# Vario_Kobo.net
KiCad netlist of a schematic drawn in EAGLE
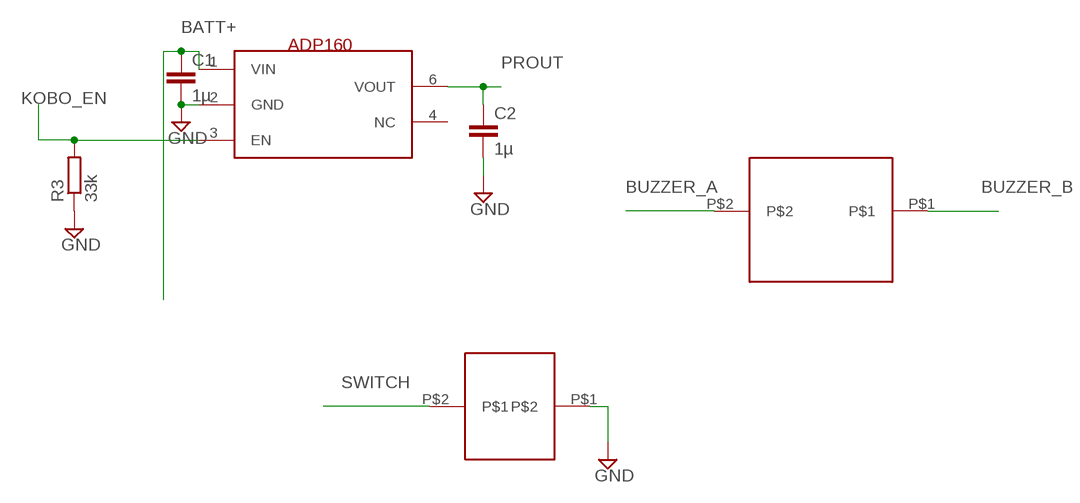
[diagram p0: schematic, sheet 1]
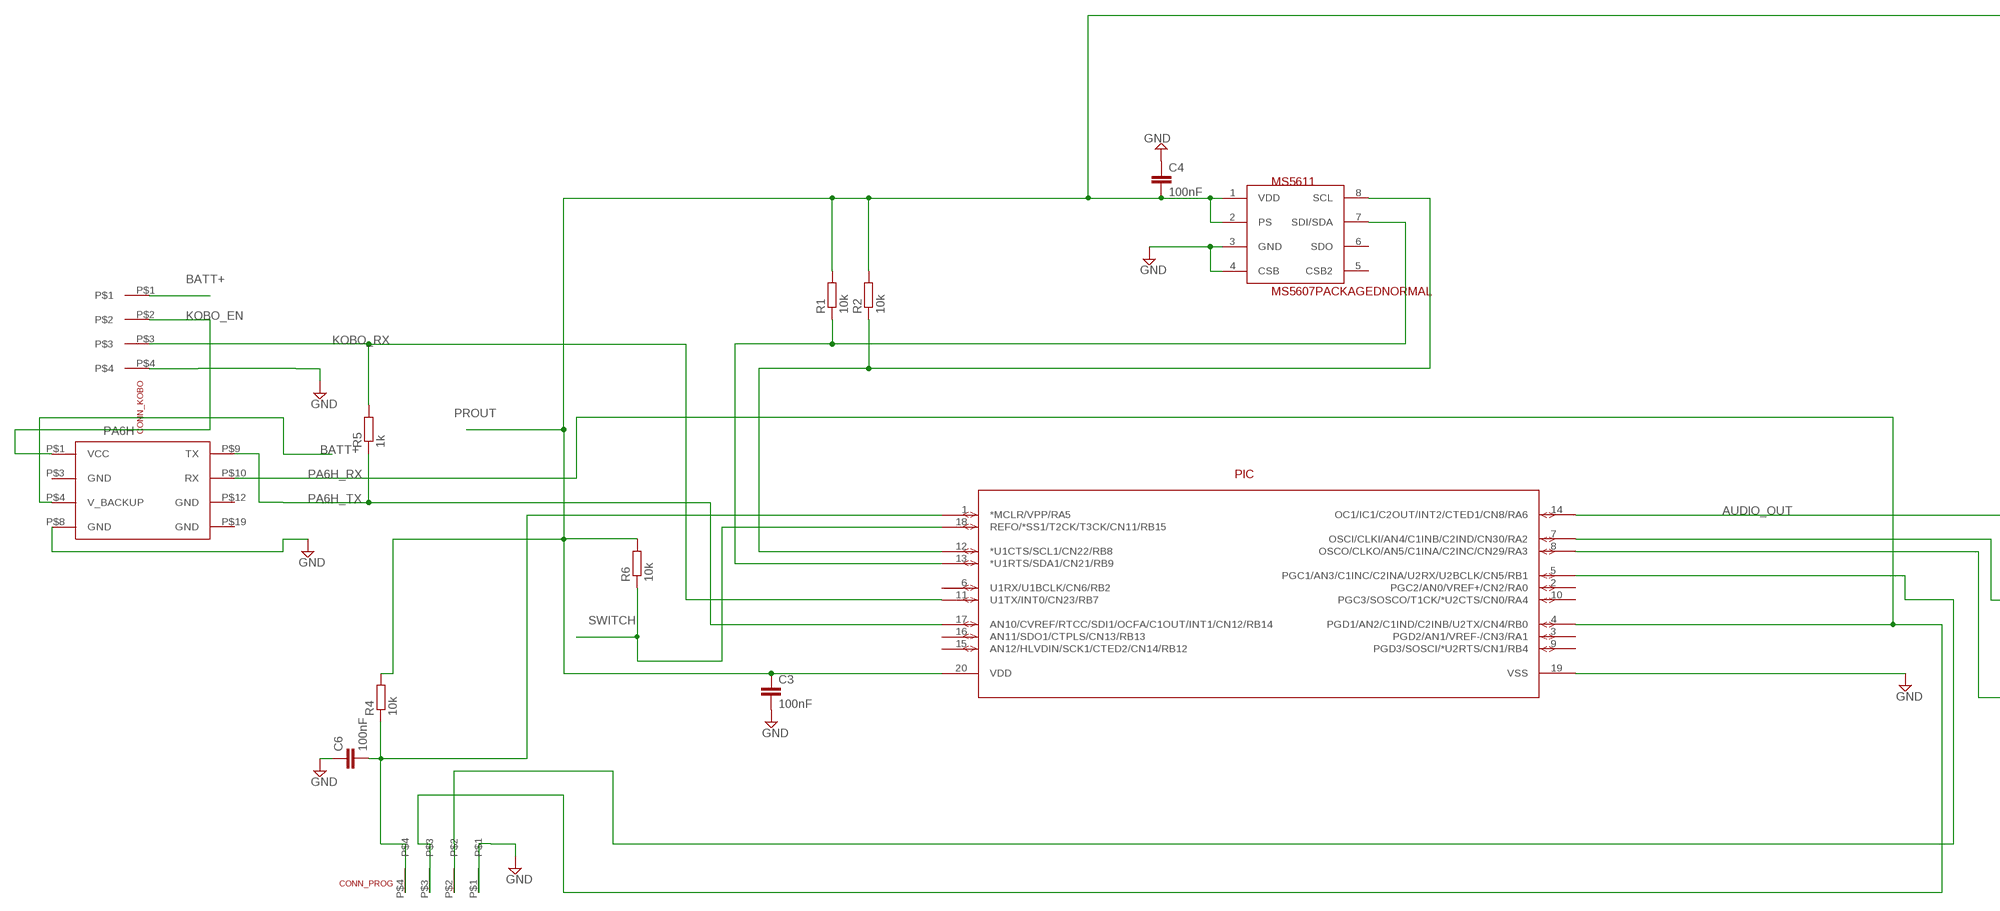
[diagram p1: schematic, sheet 2, part 1 of 2]
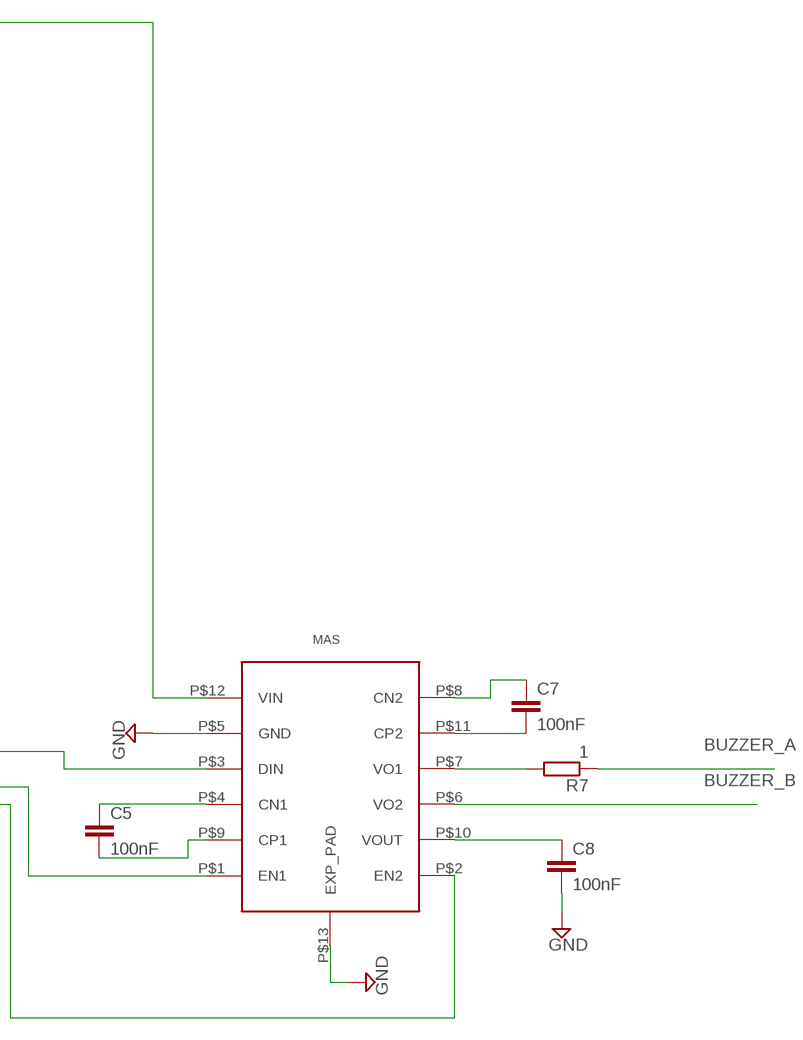
[diagram p2: schematic, sheet 2, part 2 of 2]

(export (version "E")
  (design (tool "Eeschema 10.0.6"))
  (components
    (comp (ref "ADP160")
      (value "ADP160/161/162/163")
      (footprint "eagle-import:TSOT23-6_DDC")
      (libsource (lib "eagle-import") (part "ADP160/161/162/163"))
    )
    (comp (ref "BUTTON")
      (value "SMS_J_LEAD")
      (footprint "eagle-import:SMS_J_LEAD")
      (libsource (lib "eagle-import") (part "SMS_J_LEAD"))
    )
    (comp (ref "BUZZER")
      (value "PKLCS1212E2000-R1")
      (footprint "eagle-import:PKLCS1212E2000-R1-SMD")
      (libsource (lib "eagle-import") (part "PKLCS1212E2000-R1"))
    )
    (comp (ref "C1")
      (value "1µ")
      (footprint "eagle-import:C0603")
      (libsource (lib "eagle-import") (part "C-EUC0603"))
    )
    (comp (ref "C2")
      (value "1µ")
      (footprint "eagle-import:C0603")
      (libsource (lib "eagle-import") (part "C-EUC0603"))
    )
    (comp (ref "R3")
      (value "33k")
      (footprint "eagle-import:R0603")
      (libsource (lib "eagle-import") (part "R-EU_R0603"))
    )
    (comp (ref "C3")
      (value "100nF")
      (footprint "eagle-import:C0603")
      (libsource (lib "eagle-import") (part "C-EUC0603"))
    )
    (comp (ref "C4")
      (value "100nF")
      (footprint "eagle-import:C0603")
      (libsource (lib "eagle-import") (part "C-EUC0603"))
    )
    (comp (ref "C5")
      (value "100nF")
      (footprint "eagle-import:C0603")
      (libsource (lib "eagle-import") (part "C-EUC0603"))
    )
    (comp (ref "C6")
      (value "100nF")
      (footprint "eagle-import:C0603")
      (libsource (lib "eagle-import") (part "C-EUC0603"))
    )
    (comp (ref "C7")
      (value "100nF")
      (footprint "eagle-import:C0603")
      (libsource (lib "eagle-import") (part "C-EUC0603"))
    )
    (comp (ref "C8")
      (value "100nF")
      (footprint "eagle-import:C0603")
      (libsource (lib "eagle-import") (part "C-EUC0603"))
    )
    (comp (ref "CONN_KOBO")
      (value "PICO-EZMATE4")
      (footprint "eagle-import:PICO-EZMATE4-PCB")
      (libsource (lib "eagle-import") (part "PICO-EZMATE4"))
    )
    (comp (ref "CONN_PROG")
      (value "PICO-EZMATE4")
      (footprint "eagle-import:PICO-EZMATE4-PCB")
      (libsource (lib "eagle-import") (part "PICO-EZMATE4"))
    )
    (comp (ref "MAS")
      (value "MAS6240")
      (footprint "eagle-import:QFN12_3X3_LONGPADS")
      (libsource (lib "eagle-import") (part "MAS6240"))
    )
    (comp (ref "MS5611")
      (value "MS5607PACKAGEDNORMAL")
      (footprint "eagle-import:MS5607-02BA03")
      (libsource (lib "eagle-import") (part "MS5607PACKAGEDNORMAL"))
    )
    (comp (ref "PA6H")
      (value "PA6H")
      (footprint "eagle-import:PA6H_PRINT")
      (libsource (lib "eagle-import") (part "PA6H"))
    )
    (comp (ref "PIC")
      (value "PIC24F16KA101-X_")
      (footprint "eagle-import:SSOP20_MC")
      (libsource (lib "eagle-import") (part "PIC24F16KA101-X_"))
    )
    (comp (ref "R1")
      (value "10k")
      (footprint "eagle-import:R0603")
      (libsource (lib "eagle-import") (part "R-EU_R0603"))
    )
    (comp (ref "R2")
      (value "10k")
      (footprint "eagle-import:R0603")
      (libsource (lib "eagle-import") (part "R-EU_R0603"))
    )
    (comp (ref "R4")
      (value "10k")
      (footprint "eagle-import:R0603")
      (libsource (lib "eagle-import") (part "R-EU_R0603"))
    )
    (comp (ref "R5")
      (value "1k")
      (footprint "eagle-import:R0603")
      (libsource (lib "eagle-import") (part "R-EU_R0603"))
    )
    (comp (ref "R6")
      (value "10k")
      (footprint "eagle-import:R0603")
      (libsource (lib "eagle-import") (part "R-EU_R0603"))
    )
    (comp (ref "R7")
      (value "1")
      (footprint "eagle-import:R0603")
      (libsource (lib "eagle-import") (part "R-EU_R0603"))
    )
  )
  (nets
    (net (code "1") (name "AUDIO_OUT") (class "Default")
      (node (ref "MAS") (pin "P$3") (pinfunction "DIN_P$3") (pintype "bidirectional"))
      (node (ref "PIC") (pin "14") (pinfunction "OC1/IC1/C2OUT/INT2/CTED1/CN8/RA6_14") (pintype "passive"))
    )
    (net (code "2") (name "BATT+") (class "Default")
      (node (ref "ADP160") (pin "1") (pinfunction "VIN_1") (pintype "tri_state"))
      (node (ref "C1") (pin "1") (pinfunction "1_1") (pintype "passive"))
      (node (ref "CONN_KOBO") (pin "P$1") (pinfunction "P$1_P$1") (pintype "bidirectional"))
      (node (ref "PA6H") (pin "P$4") (pinfunction "V_BACKUP_P$4") (pintype "bidirectional"))
    )
    (net (code "3") (name "BUZZER_A") (class "Default")
      (node (ref "BUZZER") (pin "P$2") (pinfunction "P$2_P$2") (pintype "bidirectional"))
      (node (ref "R7") (pin "1") (pinfunction "1_1") (pintype "passive"))
    )
    (net (code "4") (name "BUZZER_B") (class "Default")
      (node (ref "BUZZER") (pin "P$1") (pinfunction "P$1_P$1") (pintype "bidirectional"))
      (node (ref "MAS") (pin "P$6") (pinfunction "VO2_P$6") (pintype "bidirectional"))
    )
    (net (code "5") (name "GND") (class "Default")
      (node (ref "ADP160") (pin "2") (pinfunction "GND_2") (pintype "power_in"))
      (node (ref "BUTTON") (pin "P$1") (pinfunction "P$2_P$1") (pintype "bidirectional"))
      (node (ref "C1") (pin "2") (pinfunction "2_2") (pintype "passive"))
      (node (ref "C2") (pin "2") (pinfunction "2_2") (pintype "passive"))
      (node (ref "C3") (pin "2") (pinfunction "2_2") (pintype "passive"))
      (node (ref "C4") (pin "1") (pinfunction "1_1") (pintype "passive"))
      (node (ref "C6") (pin "1") (pinfunction "1_1") (pintype "passive"))
      (node (ref "C8") (pin "2") (pinfunction "2_2") (pintype "passive"))
      (node (ref "CONN_KOBO") (pin "P$4") (pinfunction "P$4_P$4") (pintype "bidirectional"))
      (node (ref "CONN_PROG") (pin "P$1") (pinfunction "P$1_P$1") (pintype "bidirectional"))
      (node (ref "MAS") (pin "P$13") (pinfunction "EXP_PAD_P$13") (pintype "bidirectional"))
      (node (ref "MAS") (pin "P$5") (pinfunction "GND_P$5") (pintype "bidirectional"))
      (node (ref "MS5611") (pin "3") (pinfunction "GND_3") (pintype "power_in"))
      (node (ref "MS5611") (pin "4") (pinfunction "CSB_4") (pintype "input"))
      (node (ref "PA6H") (pin "P$8") (pinfunction "GND_P$8") (pintype "bidirectional"))
      (node (ref "PIC") (pin "19") (pinfunction "VSS_19") (pintype "passive"))
      (node (ref "R3") (pin "1") (pinfunction "1_1") (pintype "passive"))
    )
    (net (code "6") (name "KOBO_EN") (class "Default")
      (node (ref "ADP160") (pin "3") (pinfunction "EN_3") (pintype "input"))
      (node (ref "CONN_KOBO") (pin "P$2") (pinfunction "P$2_P$2") (pintype "bidirectional"))
      (node (ref "PA6H") (pin "P$1") (pinfunction "VCC_P$1") (pintype "bidirectional"))
      (node (ref "R3") (pin "2") (pinfunction "2_2") (pintype "passive"))
    )
    (net (code "7") (name "KOBO_RX") (class "Default")
      (node (ref "CONN_KOBO") (pin "P$3") (pinfunction "P$3_P$3") (pintype "bidirectional"))
      (node (ref "PIC") (pin "11") (pinfunction "U1TX/INT0/CN23/RB7_11") (pintype "passive"))
      (node (ref "R5") (pin "2") (pinfunction "2_2") (pintype "passive"))
    )
    (net (code "8") (name "Net-(MAS-CN1)") (class "Default")
      (node (ref "C5") (pin "1") (pinfunction "1_1") (pintype "passive"))
      (node (ref "MAS") (pin "P$4") (pinfunction "CN1_P$4") (pintype "bidirectional"))
    )
    (net (code "9") (name "Net-(MAS-CN2)") (class "Default")
      (node (ref "C7") (pin "1") (pinfunction "1_1") (pintype "passive"))
      (node (ref "MAS") (pin "P$8") (pinfunction "CN2_P$8") (pintype "bidirectional"))
    )
    (net (code "10") (name "Net-(MAS-CP1)") (class "Default")
      (node (ref "C5") (pin "2") (pinfunction "2_2") (pintype "passive"))
      (node (ref "MAS") (pin "P$9") (pinfunction "CP1_P$9") (pintype "bidirectional"))
    )
    (net (code "11") (name "Net-(MAS-CP2)") (class "Default")
      (node (ref "C7") (pin "2") (pinfunction "2_2") (pintype "passive"))
      (node (ref "MAS") (pin "P$11") (pinfunction "CP2_P$11") (pintype "bidirectional"))
    )
    (net (code "12") (name "Net-(MAS-EN1)") (class "Default")
      (node (ref "MAS") (pin "P$1") (pinfunction "EN1_P$1") (pintype "bidirectional"))
      (node (ref "PIC") (pin "7") (pinfunction "OSCI/CLKI/AN4/C1INB/C2IND/CN30/RA2_7") (pintype "passive"))
    )
    (net (code "13") (name "Net-(MAS-EN2)") (class "Default")
      (node (ref "MAS") (pin "P$2") (pinfunction "EN2_P$2") (pintype "bidirectional"))
      (node (ref "PIC") (pin "8") (pinfunction "OSCO/CLKO/AN5/C1INA/C2INC/CN29/RA3_8") (pintype "passive"))
    )
    (net (code "14") (name "Net-(MAS-VO1)") (class "Default")
      (node (ref "MAS") (pin "P$7") (pinfunction "VO1_P$7") (pintype "bidirectional"))
      (node (ref "R7") (pin "2") (pinfunction "2_2") (pintype "passive"))
    )
    (net (code "15") (name "Net-(MAS-VOUT)") (class "Default")
      (node (ref "C8") (pin "1") (pinfunction "1_1") (pintype "passive"))
      (node (ref "MAS") (pin "P$10") (pinfunction "VOUT_P$10") (pintype "bidirectional"))
    )
    (net (code "16") (name "Net-(MS5611-SCL)") (class "Default")
      (node (ref "MS5611") (pin "8") (pinfunction "SCL_8") (pintype "input"))
      (node (ref "PIC") (pin "12") (pinfunction "*U1CTS/SCL1/CN22/RB8_12") (pintype "passive"))
      (node (ref "R2") (pin "1") (pinfunction "1_1") (pintype "passive"))
    )
    (net (code "17") (name "Net-(MS5611-SDI{slash}SDA)") (class "Default")
      (node (ref "MS5611") (pin "7") (pinfunction "SDI/SDA_7") (pintype "bidirectional"))
      (node (ref "PIC") (pin "13") (pinfunction "*U1RTS/SDA1/CN21/RB9_13") (pintype "passive"))
      (node (ref "R1") (pin "1") (pinfunction "1_1") (pintype "passive"))
    )
    (net (code "18") (name "Net-(PIC-*MCLR{slash}VPP{slash}RA5)") (class "Default")
      (node (ref "C6") (pin "2") (pinfunction "2_2") (pintype "passive"))
      (node (ref "CONN_PROG") (pin "P$4") (pinfunction "P$4_P$4") (pintype "bidirectional"))
      (node (ref "PIC") (pin "1") (pinfunction "*MCLR/VPP/RA5_1") (pintype "passive"))
      (node (ref "R4") (pin "1") (pinfunction "1_1") (pintype "passive"))
    )
    (net (code "19") (name "Net-(PIC-PGC1{slash}AN3{slash}C1INC{slash}C2INA{slash}U2RX{slash}U2BCLK{slash}CN5{slash}RB1)") (class "Default")
      (node (ref "CONN_PROG") (pin "P$2") (pinfunction "P$2_P$2") (pintype "bidirectional"))
      (node (ref "PIC") (pin "5") (pinfunction "PGC1/AN3/C1INC/C2INA/U2RX/U2BCLK/CN5/RB1_5") (pintype "passive"))
    )
    (net (code "20") (name "PA6H_RX") (class "Default")
      (node (ref "CONN_PROG") (pin "P$3") (pinfunction "P$3_P$3") (pintype "bidirectional"))
      (node (ref "PA6H") (pin "P$10") (pinfunction "RX_P$10") (pintype "bidirectional"))
      (node (ref "PIC") (pin "4") (pinfunction "PGD1/AN2/C1IND/C2INB/U2TX/CN4/RB0_4") (pintype "passive"))
    )
    (net (code "21") (name "PA6H_TX") (class "Default")
      (node (ref "PA6H") (pin "P$9") (pinfunction "TX_P$9") (pintype "bidirectional"))
      (node (ref "PIC") (pin "17") (pinfunction "AN10/CVREF/RTCC/SDI1/OCFA/C1OUT/INT1/CN12/RB14_17") (pintype "passive"))
      (node (ref "R5") (pin "1") (pinfunction "1_1") (pintype "passive"))
    )
    (net (code "22") (name "PROUT") (class "Default")
      (node (ref "ADP160") (pin "6") (pinfunction "VOUT_6") (pintype "bidirectional"))
      (node (ref "C2") (pin "1") (pinfunction "1_1") (pintype "passive"))
      (node (ref "C3") (pin "1") (pinfunction "1_1") (pintype "passive"))
      (node (ref "C4") (pin "2") (pinfunction "2_2") (pintype "passive"))
      (node (ref "MAS") (pin "P$12") (pinfunction "VIN_P$12") (pintype "bidirectional"))
      (node (ref "MS5611") (pin "1") (pinfunction "VDD_1") (pintype "power_in"))
      (node (ref "MS5611") (pin "2") (pinfunction "PS_2") (pintype "input"))
      (node (ref "PIC") (pin "20") (pinfunction "VDD_20") (pintype "passive"))
      (node (ref "R1") (pin "2") (pinfunction "2_2") (pintype "passive"))
      (node (ref "R2") (pin "2") (pinfunction "2_2") (pintype "passive"))
      (node (ref "R4") (pin "2") (pinfunction "2_2") (pintype "passive"))
      (node (ref "R6") (pin "2") (pinfunction "2_2") (pintype "passive"))
    )
    (net (code "23") (name "SWITCH") (class "Default")
      (node (ref "BUTTON") (pin "P$2") (pinfunction "P$1_P$2") (pintype "bidirectional"))
      (node (ref "PIC") (pin "18") (pinfunction "REFO/*SS1/T2CK/T3CK/CN11/RB15_18") (pintype "passive"))
      (node (ref "R6") (pin "1") (pinfunction "1_1") (pintype "passive"))
    )
    (net (code "24") (name "unconnected-(ADP160-NC-Pad4)") (class "Default")
      (node (ref "ADP160") (pin "4") (pinfunction "NC_4") (pintype "no_connect"))
    )
    (net (code "25") (name "unconnected-(MS5611-CSB2-Pad5)") (class "Default")
      (node (ref "MS5611") (pin "5") (pinfunction "CSB2_5") (pintype "input"))
    )
    (net (code "26") (name "unconnected-(MS5611-SDO-Pad6)") (class "Default")
      (node (ref "MS5611") (pin "6") (pinfunction "SDO_6") (pintype "output"))
    )
    (net (code "27") (name "unconnected-(PA6H-GND-PadP$3)") (class "Default")
      (node (ref "PA6H") (pin "P$3") (pinfunction "GND_P$3") (pintype "bidirectional"))
    )
    (net (code "28") (name "unconnected-(PA6H-GND-PadP$12)") (class "Default")
      (node (ref "PA6H") (pin "P$12") (pinfunction "GND_P$12") (pintype "bidirectional"))
    )
    (net (code "29") (name "unconnected-(PA6H-GND-PadP$19)") (class "Default")
      (node (ref "PA6H") (pin "P$19") (pinfunction "GND_P$19") (pintype "bidirectional"))
    )
    (net (code "30") (name "unconnected-(PIC-AN11{slash}SDO1{slash}CTPLS{slash}CN13{slash}RB13-Pad16)") (class "Default")
      (node (ref "PIC") (pin "16") (pinfunction "AN11/SDO1/CTPLS/CN13/RB13_16") (pintype "passive"))
    )
    (net (code "31") (name "unconnected-(PIC-AN12{slash}HLVDIN{slash}SCK1{slash}CTED2{slash}CN14{slash}RB12-Pad15)") (class "Default")
      (node (ref "PIC") (pin "15") (pinfunction "AN12/HLVDIN/SCK1/CTED2/CN14/RB12_15") (pintype "passive"))
    )
    (net (code "32") (name "unconnected-(PIC-PGC2{slash}AN0{slash}VREF+{slash}CN2{slash}RA0-Pad2)") (class "Default")
      (node (ref "PIC") (pin "2") (pinfunction "PGC2/AN0/VREF+/CN2/RA0_2") (pintype "passive"))
    )
    (net (code "33") (name "unconnected-(PIC-PGC3{slash}SOSCO{slash}T1CK{slash}*U2CTS{slash}CN0{slash}RA4-Pad10)") (class "Default")
      (node (ref "PIC") (pin "10") (pinfunction "PGC3/SOSCO/T1CK/*U2CTS/CN0/RA4_10") (pintype "passive"))
    )
    (net (code "34") (name "unconnected-(PIC-PGD2{slash}AN1{slash}VREF-{slash}CN3{slash}RA1-Pad3)") (class "Default")
      (node (ref "PIC") (pin "3") (pinfunction "PGD2/AN1/VREF-/CN3/RA1_3") (pintype "passive"))
    )
    (net (code "35") (name "unconnected-(PIC-PGD3{slash}SOSCI{slash}*U2RTS{slash}CN1{slash}RB4-Pad9)") (class "Default")
      (node (ref "PIC") (pin "9") (pinfunction "PGD3/SOSCI/*U2RTS/CN1/RB4_9") (pintype "passive"))
    )
    (net (code "36") (name "unconnected-(PIC-U1RX{slash}U1BCLK{slash}CN6{slash}RB2-Pad6)") (class "Default")
      (node (ref "PIC") (pin "6") (pinfunction "U1RX/U1BCLK/CN6/RB2_6") (pintype "passive"))
    )
  )
)
